# peripherals.net
KiCad netlist of a schematic drawn in Altium Designer
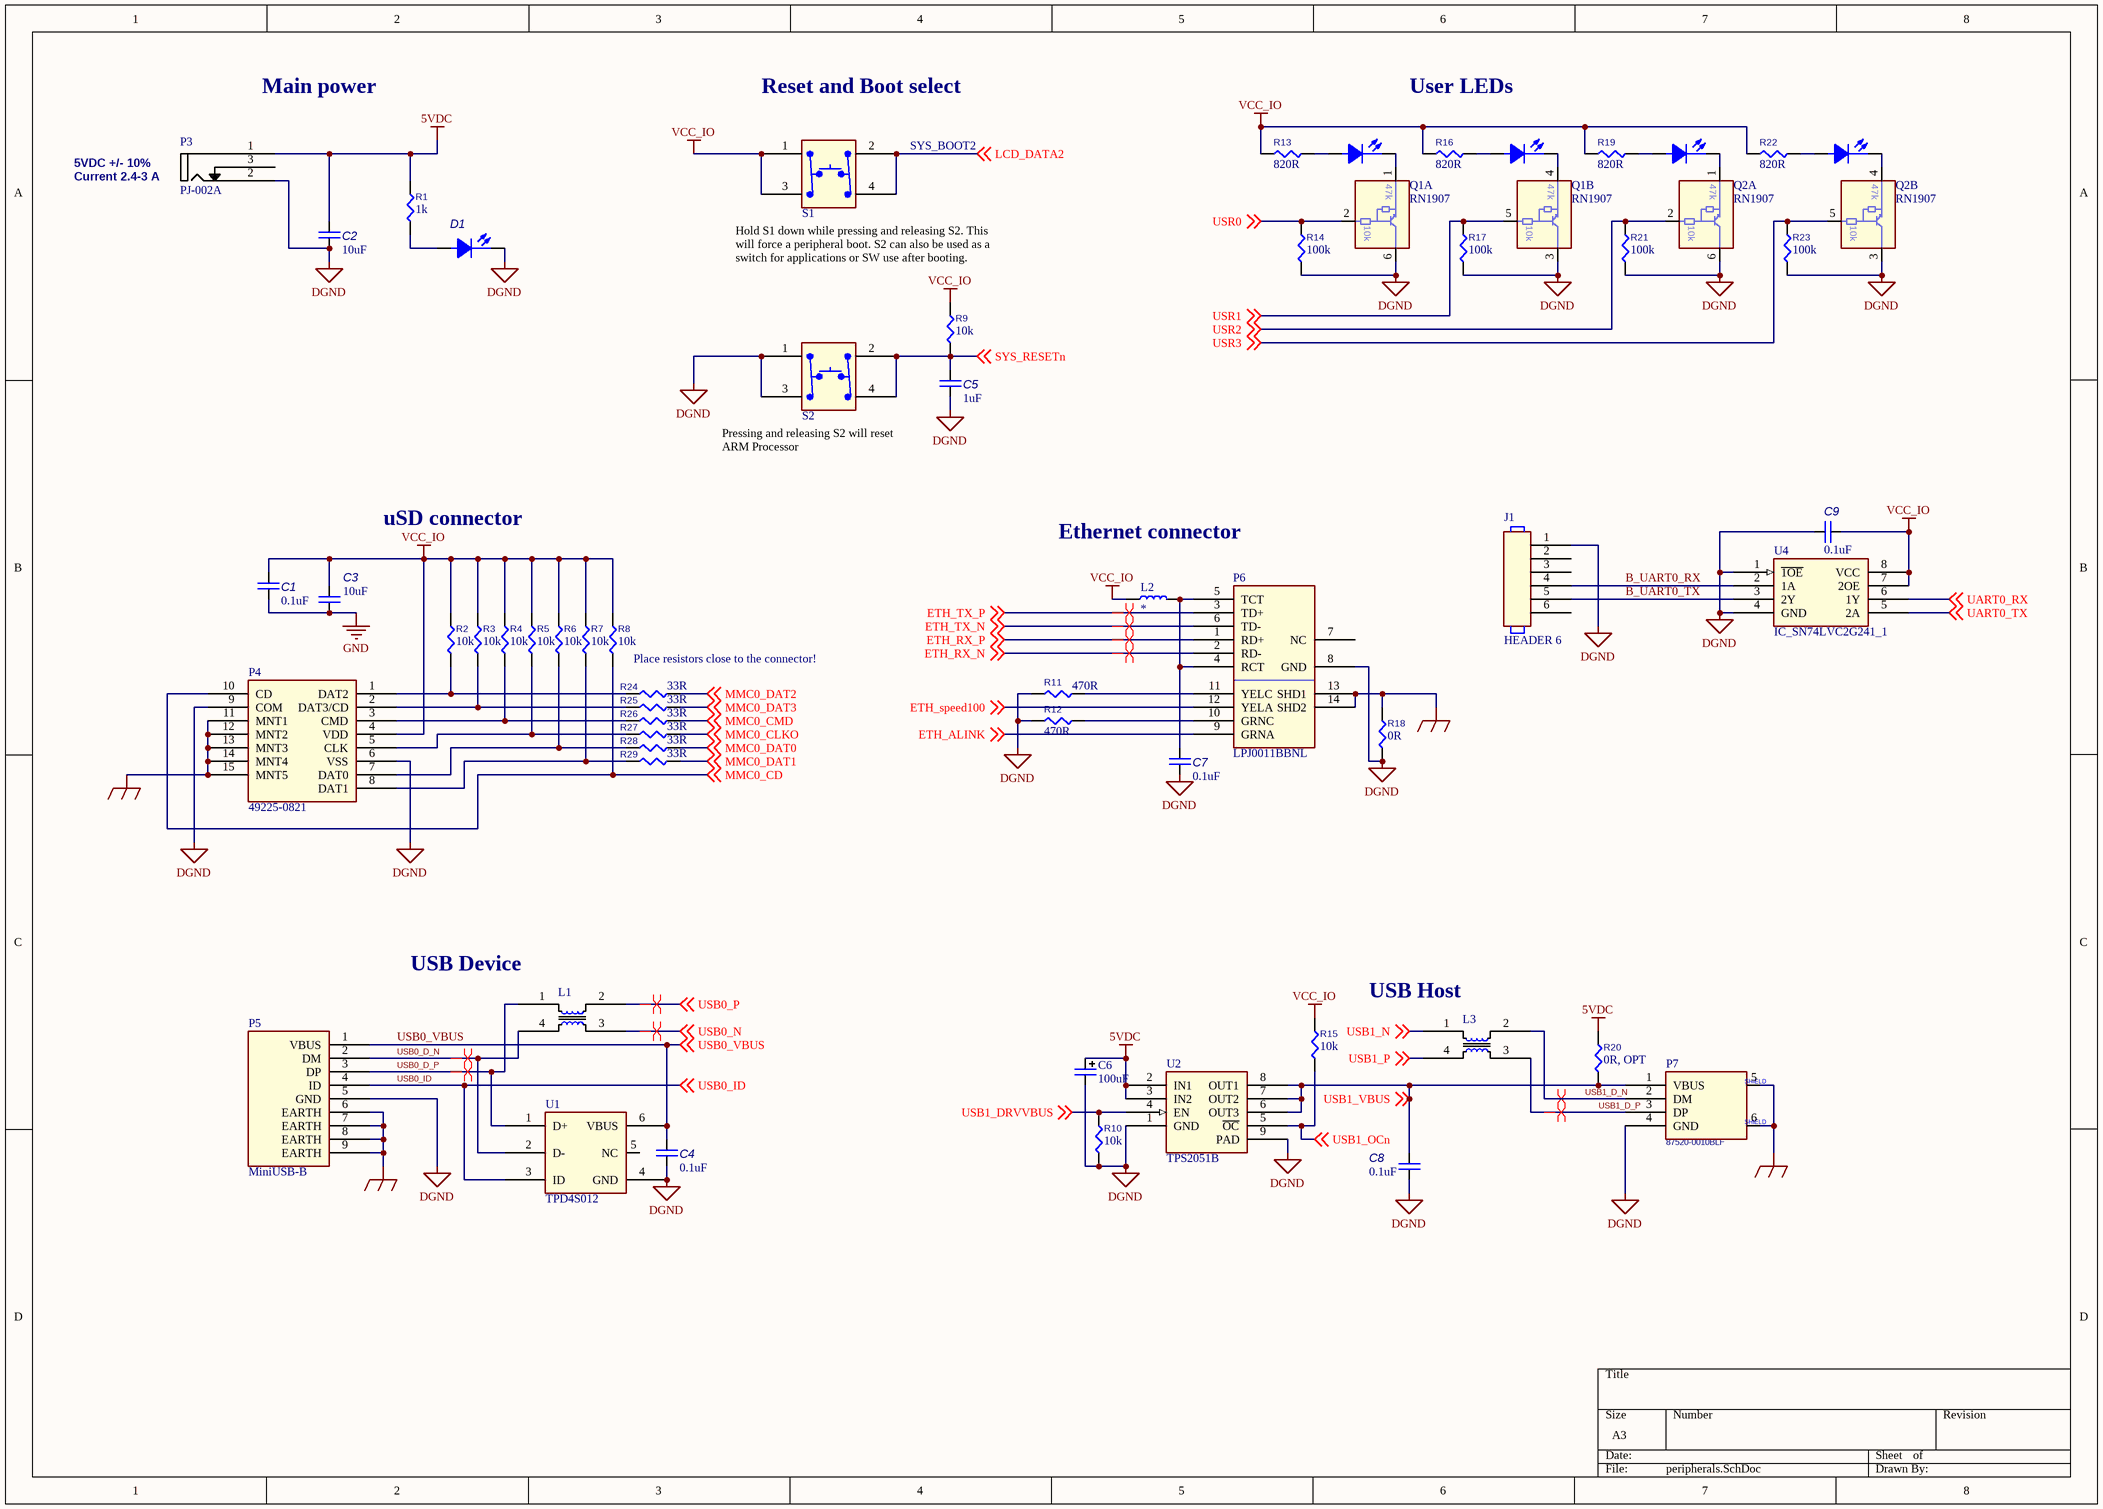
[diagram p0: peripherals.SchDoc]

(export (version "E")
  (design (tool "Eeschema 10.0.6"))
  (components
    (comp (ref "C1")
      (value "0.1uF")
      (footprint "CC1608-0603")
      (description "C0603")
      (libsource (lib "am335x-base") (part "C0603"))
    )
    (comp (ref "C2")
      (value "10uF")
      (footprint "CC2012-0805")
      (description "C0805")
      (libsource (lib "am335x-base") (part "C0805"))
    )
    (comp (ref "C3")
      (value "10uF")
      (footprint "CC2012-0805")
      (description "C0805")
      (libsource (lib "am335x-base") (part "C0805"))
    )
    (comp (ref "C4")
      (value "0.1uF")
      (footprint "CC1608-0603")
      (description "C0603")
      (libsource (lib "am335x-base") (part "C0603"))
    )
    (comp (ref "C5")
      (value "1uF")
      (footprint "CC1608-0603")
      (description "C0603")
      (libsource (lib "am335x-base") (part "C0603"))
    )
    (comp (ref "C6")
      (value "100uF")
      (footprint "Cap_C")
      (description "Tantalum Capacitor Case C")
      (fields (field (name "Comment") "Cap_C"))
      (libsource (lib "am335x-base") (part "Cap_C"))
    )
    (comp (ref "C7")
      (value "0.1uF")
      (footprint "CC1608-0603")
      (description "C0603")
      (libsource (lib "am335x-base") (part "C0603"))
    )
    (comp (ref "C8")
      (value "0.1uF")
      (footprint "CC1608-0603")
      (description "C0603")
      (libsource (lib "am335x-base") (part "C0603"))
    )
    (comp (ref "C9")
      (value "0.1uF")
      (footprint "CC1608-0603")
      (description "C0603")
      (libsource (lib "usomiq-base") (part "C0603"))
    )
    (comp (ref "D1")
      (value "LED0805")
      (footprint "LED0805")
      (description "LED 0805")
      (libsource (lib "am335x-base") (part "LED0805"))
    )
    (comp (ref "D2")
      (value "LED0805")
      (footprint "LED0805")
      (description "LED 0805")
      (libsource (lib "am335x-base") (part "LED0805"))
    )
    (comp (ref "D3")
      (value "LED0805")
      (footprint "LED0805")
      (description "LED 0805")
      (libsource (lib "am335x-base") (part "LED0805"))
    )
    (comp (ref "D4")
      (value "LED0805")
      (footprint "LED0805")
      (description "LED 0805")
      (libsource (lib "am335x-base") (part "LED0805"))
    )
    (comp (ref "D5")
      (value "LED0805")
      (footprint "LED0805")
      (description "LED 0805")
      (libsource (lib "am335x-base") (part "LED0805"))
    )
    (comp (ref "J1")
      (value "HEADER 6")
      (footprint "DIP6")
      (description "CONN HEADER 6POS, VERTICAL,  .100 STR TIN")
      (fields (field (name "MFR") "FCI"))
      (libsource (lib "usomiq-base") (part "HEADER 6"))
    )
    (comp (ref "L1")
      (value "DLW21H")
      (footprint "DLW21H")
      (description "Low profile wire-wound common choke coil")
      (fields (field (name "MANUFACTURER") "Murata"))
      (libsource (lib "am335x-base") (part "DLW21H"))
    )
    (comp (ref "L2")
      (value "BLM18A-FB")
      (footprint "CHIP0603")
      (description "Chip EMIFILr Inductor Type")
      (fields (field (name "MANUFACTURER") "Murata") (field (name "MAN P/N") "*"))
      (libsource (lib "am335x-base") (part "BLM18A-FB"))
    )
    (comp (ref "L3")
      (value "DLW21H")
      (footprint "DLW21H")
      (description "Low profile wire-wound common choke coil")
      (fields (field (name "MANUFACTURER") "Murata"))
      (libsource (lib "am335x-base") (part "DLW21H"))
    )
    (comp (ref "P3")
      (value "PJ-002A")
      (footprint "PJ-002A")
      (description "DC POWER JACK")
      (fields (field (name "MANUFACTURER") "CIU Inc"))
      (libsource (lib "omap") (part "PJ-002A"))
    )
    (comp (ref "P4")
      (value "49225-0821")
      (footprint "SDCard")
      (description "Connector for microSD™ Card (Push-push Type)")
      (fields (field (name "MANUFACTURER") "Molex"))
      (libsource (lib "am335x-base") (part "Mol_49225-0821"))
    )
    (comp (ref "P5")
      (value "MiniUSB-B")
      (footprint "MINI-USB-B5 SMT")
      (description "Mini USB Type B CONNECTOR")
      (fields (field (name "MFR") "Hirose"))
      (libsource (lib "usomiq-base") (part "MiniUSB-B"))
    )
    (comp (ref "P6")
      (value "CONN_RJ45_MAG_WE_0")
      (footprint "TRJ0011ABNL")
      (description "RJ-45 10/100 W/Magnetics")
      (fields (field (name "MFR") "Link PP") (field (name "P/N") "LPJ0011BBNL"))
      (libsource (lib "am335x-base") (part "CONN_RJ45_MAG_WE_0"))
    )
    (comp (ref "P7")
      (value "CONN_54819-0578_2")
      (footprint "USB2.5-2H4C")
      (description "USB Type A Connectors")
      (fields (field (name "P/N") "87520-0010BLF") (field (name "MFR") "FCI"))
      (libsource (lib "am335x-base") (part "CONN_54819-0578_2"))
    )
    (comp (ref "Q1")
      (value "RN1907")
      (footprint "SOT363-6L")
      (description "Transistor Silicon NPN")
      (fields (field (name "MFR") "Panasonic"))
      (libsource (lib "am335x-base") (part "RN1907"))
    )
    (comp (ref "Q2")
      (value "RN1907")
      (footprint "SOT363-6L")
      (description "Transistor Silicon NPN")
      (fields (field (name "MFR") "Panasonic"))
      (libsource (lib "am335x-base") (part "RN1907"))
    )
    (comp (ref "R1")
      (value "1k")
      (footprint "RESC1608X55N")
      (description "R0603")
      (libsource (lib "am335x-base") (part "R0603"))
    )
    (comp (ref "R2")
      (value "10k")
      (footprint "RESC1608X55N")
      (description "R0603")
      (libsource (lib "am335x-base") (part "R0603"))
    )
    (comp (ref "R3")
      (value "10k")
      (footprint "RESC1608X55N")
      (description "R0603")
      (libsource (lib "am335x-base") (part "R0603"))
    )
    (comp (ref "R4")
      (value "10k")
      (footprint "RESC1608X55N")
      (description "R0603")
      (libsource (lib "am335x-base") (part "R0603"))
    )
    (comp (ref "R5")
      (value "10k")
      (footprint "RESC1608X55N")
      (description "R0603")
      (libsource (lib "am335x-base") (part "R0603"))
    )
    (comp (ref "R6")
      (value "10k")
      (footprint "RESC1608X55N")
      (description "R0603")
      (libsource (lib "am335x-base") (part "R0603"))
    )
    (comp (ref "R7")
      (value "10k")
      (footprint "RESC1608X55N")
      (description "R0603")
      (libsource (lib "am335x-base") (part "R0603"))
    )
    (comp (ref "R8")
      (value "10k")
      (footprint "RESC1608X55N")
      (description "R0603")
      (libsource (lib "am335x-base") (part "R0603"))
    )
    (comp (ref "R9")
      (value "10k")
      (footprint "RESC1608X55N")
      (description "R0603")
      (libsource (lib "am335x-base") (part "R0603"))
    )
    (comp (ref "R10")
      (value "10k")
      (footprint "RESC1608X55N")
      (description "R0603")
      (libsource (lib "am335x-base") (part "R0603"))
    )
    (comp (ref "R11")
      (value "470R")
      (footprint "RESC1608X55N")
      (description "R0603")
      (libsource (lib "am335x-base") (part "R0603"))
    )
    (comp (ref "R12")
      (value "470R")
      (footprint "RESC1608X55N")
      (description "R0603")
      (libsource (lib "am335x-base") (part "R0603"))
    )
    (comp (ref "R13")
      (value "820R")
      (footprint "RESC1608X55N")
      (description "R0603")
      (libsource (lib "am335x-base") (part "R0603"))
    )
    (comp (ref "R14")
      (value "100k")
      (footprint "RESC1608X55N")
      (description "R0603")
      (libsource (lib "am335x-base") (part "R0603"))
    )
    (comp (ref "R15")
      (value "10k")
      (footprint "RESC1608X55N")
      (description "R0603")
      (libsource (lib "am335x-base") (part "R0603"))
    )
    (comp (ref "R16")
      (value "820R")
      (footprint "RESC1608X55N")
      (description "R0603")
      (libsource (lib "am335x-base") (part "R0603"))
    )
    (comp (ref "R17")
      (value "100k")
      (footprint "RESC1608X55N")
      (description "R0603")
      (libsource (lib "am335x-base") (part "R0603"))
    )
    (comp (ref "R18")
      (value "0R")
      (footprint "RESC1608X55N")
      (description "R0603")
      (libsource (lib "am335x-base") (part "R0603"))
    )
    (comp (ref "R19")
      (value "820R")
      (footprint "RESC1608X55N")
      (description "R0603")
      (libsource (lib "am335x-base") (part "R0603"))
    )
    (comp (ref "R20")
      (value "0R, OPT")
      (footprint "RESC1608X55N")
      (description "R0603")
      (libsource (lib "am335x-base") (part "R0603"))
    )
    (comp (ref "R21")
      (value "100k")
      (footprint "RESC1608X55N")
      (description "R0603")
      (libsource (lib "am335x-base") (part "R0603"))
    )
    (comp (ref "R22")
      (value "820R")
      (footprint "RESC1608X55N")
      (description "R0603")
      (libsource (lib "am335x-base") (part "R0603"))
    )
    (comp (ref "R23")
      (value "100k")
      (footprint "RESC1608X55N")
      (description "R0603")
      (libsource (lib "am335x-base") (part "R0603"))
    )
    (comp (ref "R24")
      (value "33R")
      (footprint "RESC1608X55N")
      (description "R0603")
      (libsource (lib "usomiq-base") (part "R0603"))
    )
    (comp (ref "R25")
      (value "33R")
      (footprint "RESC1608X55N")
      (description "R0603")
      (libsource (lib "usomiq-base") (part "R0603"))
    )
    (comp (ref "R26")
      (value "33R")
      (footprint "RESC1608X55N")
      (description "R0603")
      (libsource (lib "usomiq-base") (part "R0603"))
    )
    (comp (ref "R27")
      (value "33R")
      (footprint "RESC1608X55N")
      (description "R0603")
      (libsource (lib "usomiq-base") (part "R0603"))
    )
    (comp (ref "R28")
      (value "33R")
      (footprint "RESC1608X55N")
      (description "R0603")
      (libsource (lib "usomiq-base") (part "R0603"))
    )
    (comp (ref "R29")
      (value "33R")
      (footprint "RESC1608X55N")
      (description "R0603")
      (libsource (lib "usomiq-base") (part "R0603"))
    )
    (comp (ref "S1")
      (value "SW_KT11P2JM_2")
      (footprint "KMR231GLFS")
      (description "SMD button")
      (fields (field (name "MFR") "C&K Components"))
      (libsource (lib "usomiq-base") (part "SW_KT11P2JM_2"))
    )
    (comp (ref "S2")
      (value "SW_KT11P2JM_2")
      (footprint "KMR231GLFS")
      (description "SMD button")
      (fields (field (name "MFR") "C&K Components"))
      (libsource (lib "usomiq-base") (part "SW_KT11P2JM_2"))
    )
    (comp (ref "U1")
      (value "TPD4S012")
      (footprint "s-puson-n6")
      (description "4-Channel USB ESD Solution with Power Clamp")
      (fields (field (name "MFR") "TI"))
      (libsource (lib "usomiq-base") (part "TPD4S012"))
    )
    (comp (ref "U2")
      (value "TPS2051B")
      (footprint "R-PDSO-G8")
      (description "CURRENT-LIMITED, POWER-DISTRIBUTION SWITCHES")
      (fields (field (name "MFR") "TI"))
      (libsource (lib "usomiq-base") (part "TPS2051B"))
    )
    (comp (ref "U4")
      (value "IC_SN74LVC2G241_1")
      (footprint "SOP127P600-8N")
      (description "Dual Buffer/Driver With 3-State Outputs")
      (fields (field (name "MFR") "TI"))
      (libsource (lib "usomiq-base") (part "IC_SN74LVC2G241_1"))
    )
  )
  (nets
    (net (code "1") (name "/B_UART0_RX") (class "Default")
      (node (ref "J1") (pin "4") (pinfunction "4_4") (pintype "passive"))
      (node (ref "U4") (pin "2") (pinfunction "1A_2") (pintype "passive"))
    )
    (net (code "2") (name "/B_UART0_TX") (class "Default")
      (node (ref "J1") (pin "5") (pinfunction "5_5") (pintype "passive"))
      (node (ref "U4") (pin "3") (pinfunction "2Y_3") (pintype "passive"))
    )
    (net (code "3") (name "/USB0_D_N") (class "Default")
      (node (ref "L1") (pin "4") (pinfunction "4_4") (pintype "passive"))
      (node (ref "P5") (pin "2") (pinfunction "DM_2") (pintype "passive"))
      (node (ref "U1") (pin "2") (pinfunction "D-_2") (pintype "passive"))
    )
    (net (code "4") (name "/USB0_D_P") (class "Default")
      (node (ref "L1") (pin "1") (pinfunction "1_1") (pintype "passive"))
      (node (ref "P5") (pin "3") (pinfunction "DP_3") (pintype "passive"))
      (node (ref "U1") (pin "1") (pinfunction "D+_1") (pintype "passive"))
    )
    (net (code "5") (name "/USB1_D_N") (class "Default")
      (node (ref "L3") (pin "2") (pinfunction "2_2") (pintype "passive"))
      (node (ref "P7") (pin "2") (pinfunction "DM_2") (pintype "passive"))
    )
    (net (code "6") (name "/USB1_D_P") (class "Default")
      (node (ref "L3") (pin "3") (pinfunction "3_3") (pintype "passive"))
      (node (ref "P7") (pin "3") (pinfunction "DP_3") (pintype "passive"))
    )
    (net (code "7") (name "5VDC") (class "Default")
      (node (ref "C2") (pin "2") (pinfunction "2_2") (pintype "passive"))
      (node (ref "C6") (pin "1") (pinfunction "1_1") (pintype "passive"))
      (node (ref "P3") (pin "1") (pinfunction "GND_1") (pintype "passive"))
      (node (ref "R1") (pin "2") (pinfunction "2_2") (pintype "passive"))
      (node (ref "R20") (pin "2") (pinfunction "2_2") (pintype "passive"))
      (node (ref "U2") (pin "2") (pinfunction "IN1_2") (pintype "power_in"))
      (node (ref "U2") (pin "3") (pinfunction "IN2_3") (pintype "power_in"))
    )
    (net (code "8") (name "DGND") (class "Default")
      (node (ref "C2") (pin "1") (pinfunction "1_1") (pintype "passive"))
      (node (ref "C4") (pin "2") (pinfunction "2_2") (pintype "passive"))
      (node (ref "C5") (pin "2") (pinfunction "2_2") (pintype "passive"))
      (node (ref "C6") (pin "2") (pinfunction "2_2") (pintype "passive"))
      (node (ref "C7") (pin "2") (pinfunction "2_2") (pintype "passive"))
      (node (ref "C8") (pin "1") (pinfunction "1_1") (pintype "passive"))
      (node (ref "C9") (pin "1") (pinfunction "1_1") (pintype "passive"))
      (node (ref "D1") (pin "2") (pinfunction "C_2") (pintype "passive"))
      (node (ref "J1") (pin "1") (pinfunction "1_1") (pintype "passive"))
      (node (ref "P3") (pin "2") (pinfunction "RIGHT_2") (pintype "passive"))
      (node (ref "P4") (pin "6") (pinfunction "VSS_6") (pintype "power_in"))
      (node (ref "P4") (pin "9") (pinfunction "COM_9") (pintype "passive"))
      (node (ref "P5") (pin "5") (pinfunction "GND_5") (pintype "power_in"))
      (node (ref "P6") (pin "8") (pinfunction "GND_8") (pintype "passive"))
      (node (ref "P7") (pin "4") (pinfunction "GND_4") (pintype "passive"))
      (node (ref "Q1") (pin "3") (pinfunction "3_3") (pintype "passive"))
      (node (ref "Q1") (pin "6") (pinfunction "3_6") (pintype "passive"))
      (node (ref "Q2") (pin "3") (pinfunction "3_3") (pintype "passive"))
      (node (ref "Q2") (pin "6") (pinfunction "3_6") (pintype "passive"))
      (node (ref "R10") (pin "1") (pinfunction "1_1") (pintype "passive"))
      (node (ref "R11") (pin "1") (pinfunction "1_1") (pintype "passive"))
      (node (ref "R12") (pin "1") (pinfunction "1_1") (pintype "passive"))
      (node (ref "R14") (pin "1") (pinfunction "1_1") (pintype "passive"))
      (node (ref "R17") (pin "1") (pinfunction "1_1") (pintype "passive"))
      (node (ref "R18") (pin "1") (pinfunction "1_1") (pintype "passive"))
      (node (ref "R21") (pin "1") (pinfunction "1_1") (pintype "passive"))
      (node (ref "R23") (pin "1") (pinfunction "1_1") (pintype "passive"))
      (node (ref "S2") (pin "1") (pinfunction "A1_1") (pintype "passive"))
      (node (ref "S2") (pin "3") (pinfunction "A2_3") (pintype "passive"))
      (node (ref "U1") (pin "4") (pinfunction "GND_4") (pintype "power_in"))
      (node (ref "U2") (pin "1") (pinfunction "GND_1") (pintype "power_in"))
      (node (ref "U2") (pin "9") (pinfunction "PAD_9") (pintype "passive"))
      (node (ref "U4") (pin "1") (pinfunction "~{1OE}_1") (pintype "input"))
      (node (ref "U4") (pin "4") (pinfunction "GND_4") (pintype "power_in"))
    )
    (net (code "9") (name "EARTH") (class "Default")
      (node (ref "P4") (pin "11") (pinfunction "MNT1_11") (pintype "passive"))
      (node (ref "P4") (pin "12") (pinfunction "MNT2_12") (pintype "passive"))
      (node (ref "P4") (pin "13") (pinfunction "MNT3_13") (pintype "passive"))
      (node (ref "P4") (pin "14") (pinfunction "MNT4_14") (pintype "passive"))
      (node (ref "P4") (pin "15") (pinfunction "MNT5_15") (pintype "passive"))
      (node (ref "P5") (pin "6") (pinfunction "EARTH_6") (pintype "passive"))
      (node (ref "P5") (pin "7") (pinfunction "EARTH_7") (pintype "passive"))
      (node (ref "P5") (pin "8") (pinfunction "EARTH_8") (pintype "passive"))
      (node (ref "P5") (pin "9") (pinfunction "EARTH_9") (pintype "passive"))
      (node (ref "P6") (pin "13") (pinfunction "SHD1_13") (pintype "passive"))
      (node (ref "P6") (pin "14") (pinfunction "SHD2_14") (pintype "passive"))
      (node (ref "P7") (pin "5") (pinfunction "SHELD1_5") (pintype "passive"))
      (node (ref "P7") (pin "6") (pinfunction "PAD4_6") (pintype "passive"))
      (node (ref "R18") (pin "2") (pinfunction "2_2") (pintype "passive"))
    )
    (net (code "10") (name "ETH_ALINK") (class "Default")
      (node (ref "P6") (pin "9") (pinfunction "GRNA_9") (pintype "passive"))
    )
    (net (code "11") (name "ETH_RX_N") (class "Default")
      (node (ref "P6") (pin "2") (pinfunction "RD-_2") (pintype "passive"))
    )
    (net (code "12") (name "ETH_RX_P") (class "Default")
      (node (ref "P6") (pin "1") (pinfunction "RD+_1") (pintype "passive"))
    )
    (net (code "13") (name "ETH_TX_N") (class "Default")
      (node (ref "P6") (pin "6") (pinfunction "TD-_6") (pintype "passive"))
    )
    (net (code "14") (name "ETH_TX_P") (class "Default")
      (node (ref "P6") (pin "3") (pinfunction "TD+_3") (pintype "passive"))
    )
    (net (code "15") (name "ETH_speed100") (class "Default")
      (node (ref "P6") (pin "12") (pinfunction "YELA_12") (pintype "passive"))
    )
    (net (code "16") (name "GND") (class "Default")
      (node (ref "C1") (pin "2") (pinfunction "2_2") (pintype "passive"))
      (node (ref "C3") (pin "1") (pinfunction "1_1") (pintype "passive"))
    )
    (net (code "17") (name "LCD_DATA2") (class "Default")
      (node (ref "S1") (pin "2") (pinfunction "B1_2") (pintype "passive"))
      (node (ref "S1") (pin "4") (pinfunction "B2_4") (pintype "passive"))
    )
    (net (code "18") (name "MMC0_CD") (class "Default")
      (node (ref "P4") (pin "10") (pinfunction "CD_10") (pintype "passive"))
      (node (ref "R8") (pin "1") (pinfunction "1_1") (pintype "passive"))
    )
    (net (code "19") (name "MMC0_CLKO") (class "Default")
      (node (ref "R27") (pin "2") (pinfunction "2_2") (pintype "passive"))
    )
    (net (code "20") (name "MMC0_CMD") (class "Default")
      (node (ref "R26") (pin "2") (pinfunction "2_2") (pintype "passive"))
    )
    (net (code "21") (name "MMC0_DAT0") (class "Default")
      (node (ref "R28") (pin "2") (pinfunction "2_2") (pintype "passive"))
    )
    (net (code "22") (name "MMC0_DAT1") (class "Default")
      (node (ref "R29") (pin "2") (pinfunction "2_2") (pintype "passive"))
    )
    (net (code "23") (name "MMC0_DAT2") (class "Default")
      (node (ref "R24") (pin "2") (pinfunction "2_2") (pintype "passive"))
    )
    (net (code "24") (name "MMC0_DAT3") (class "Default")
      (node (ref "R25") (pin "2") (pinfunction "2_2") (pintype "passive"))
    )
    (net (code "25") (name "Net-(D1-A)") (class "Default")
      (node (ref "D1") (pin "1") (pinfunction "A_1") (pintype "passive"))
      (node (ref "R1") (pin "1") (pinfunction "1_1") (pintype "passive"))
    )
    (net (code "26") (name "Net-(D2-A)") (class "Default")
      (node (ref "D2") (pin "1") (pinfunction "A_1") (pintype "passive"))
      (node (ref "R13") (pin "1") (pinfunction "1_1") (pintype "passive"))
    )
    (net (code "27") (name "Net-(D2-C)") (class "Default")
      (node (ref "D2") (pin "2") (pinfunction "C_2") (pintype "passive"))
      (node (ref "Q1") (pin "1") (pinfunction "4_1") (pintype "passive"))
    )
    (net (code "28") (name "Net-(D3-A)") (class "Default")
      (node (ref "D3") (pin "1") (pinfunction "A_1") (pintype "passive"))
      (node (ref "R16") (pin "1") (pinfunction "1_1") (pintype "passive"))
    )
    (net (code "29") (name "Net-(D3-C)") (class "Default")
      (node (ref "D3") (pin "2") (pinfunction "C_2") (pintype "passive"))
      (node (ref "Q1") (pin "4") (pinfunction "4_4") (pintype "passive"))
    )
    (net (code "30") (name "Net-(D4-A)") (class "Default")
      (node (ref "D4") (pin "1") (pinfunction "A_1") (pintype "passive"))
      (node (ref "R19") (pin "1") (pinfunction "1_1") (pintype "passive"))
    )
    (net (code "31") (name "Net-(D4-C)") (class "Default")
      (node (ref "D4") (pin "2") (pinfunction "C_2") (pintype "passive"))
      (node (ref "Q2") (pin "1") (pinfunction "4_1") (pintype "passive"))
    )
    (net (code "32") (name "Net-(D5-A)") (class "Default")
      (node (ref "D5") (pin "1") (pinfunction "A_1") (pintype "passive"))
      (node (ref "R22") (pin "1") (pinfunction "1_1") (pintype "passive"))
    )
    (net (code "33") (name "Net-(D5-C)") (class "Default")
      (node (ref "D5") (pin "2") (pinfunction "C_2") (pintype "passive"))
      (node (ref "Q2") (pin "4") (pinfunction "4_4") (pintype "passive"))
    )
    (net (code "34") (name "Net-(P4-CLK)") (class "Default")
      (node (ref "P4") (pin "5") (pinfunction "CLK_5") (pintype "passive"))
      (node (ref "R27") (pin "1") (pinfunction "1_1") (pintype "passive"))
      (node (ref "R5") (pin "1") (pinfunction "1_1") (pintype "passive"))
    )
    (net (code "35") (name "Net-(P4-CMD)") (class "Default")
      (node (ref "P4") (pin "3") (pinfunction "CMD_3") (pintype "passive"))
      (node (ref "R26") (pin "1") (pinfunction "1_1") (pintype "passive"))
      (node (ref "R4") (pin "1") (pinfunction "1_1") (pintype "passive"))
    )
    (net (code "36") (name "Net-(P4-DAT0)") (class "Default")
      (node (ref "P4") (pin "7") (pinfunction "DAT0_7") (pintype "passive"))
      (node (ref "R28") (pin "1") (pinfunction "1_1") (pintype "passive"))
      (node (ref "R6") (pin "1") (pinfunction "1_1") (pintype "passive"))
    )
    (net (code "37") (name "Net-(P4-DAT1)") (class "Default")
      (node (ref "P4") (pin "8") (pinfunction "DAT1_8") (pintype "passive"))
      (node (ref "R29") (pin "1") (pinfunction "1_1") (pintype "passive"))
      (node (ref "R7") (pin "1") (pinfunction "1_1") (pintype "passive"))
    )
    (net (code "38") (name "Net-(P4-DAT2)") (class "Default")
      (node (ref "P4") (pin "1") (pinfunction "DAT2_1") (pintype "passive"))
      (node (ref "R2") (pin "1") (pinfunction "1_1") (pintype "passive"))
      (node (ref "R24") (pin "1") (pinfunction "1_1") (pintype "passive"))
    )
    (net (code "39") (name "Net-(P4-DAT3{slash}CD)") (class "Default")
      (node (ref "P4") (pin "2") (pinfunction "DAT3/CD_2") (pintype "passive"))
      (node (ref "R25") (pin "1") (pinfunction "1_1") (pintype "passive"))
      (node (ref "R3") (pin "1") (pinfunction "1_1") (pintype "passive"))
    )
    (net (code "40") (name "Net-(P6-GRNC)") (class "Default")
      (node (ref "P6") (pin "10") (pinfunction "GRNC_10") (pintype "passive"))
      (node (ref "R12") (pin "2") (pinfunction "2_2") (pintype "passive"))
    )
    (net (code "41") (name "Net-(P6-RCT)") (class "Default")
      (node (ref "C7") (pin "1") (pinfunction "1_1") (pintype "passive"))
      (node (ref "L2") (pin "2") (pinfunction "2_2") (pintype "passive"))
      (node (ref "P6") (pin "4") (pinfunction "RCT_4") (pintype "passive"))
      (node (ref "P6") (pin "5") (pinfunction "TCT_5") (pintype "passive"))
    )
    (net (code "42") (name "Net-(P6-YELC)") (class "Default")
      (node (ref "P6") (pin "11") (pinfunction "YELC_11") (pintype "passive"))
      (node (ref "R11") (pin "2") (pinfunction "2_2") (pintype "passive"))
    )
    (net (code "43") (name "SYS_RESETn") (class "Default")
      (node (ref "C5") (pin "1") (pinfunction "1_1") (pintype "passive"))
      (node (ref "R9") (pin "1") (pinfunction "1_1") (pintype "passive"))
      (node (ref "S2") (pin "2") (pinfunction "B1_2") (pintype "passive"))
      (node (ref "S2") (pin "4") (pinfunction "B2_4") (pintype "passive"))
    )
    (net (code "44") (name "UART0_RX") (class "Default")
      (node (ref "U4") (pin "6") (pinfunction "1Y_6") (pintype "passive"))
    )
    (net (code "45") (name "UART0_TX") (class "Default")
      (node (ref "U4") (pin "5") (pinfunction "2A_5") (pintype "passive"))
    )
    (net (code "46") (name "USB0_ID") (class "Default")
      (node (ref "P5") (pin "4") (pinfunction "ID_4") (pintype "passive"))
      (node (ref "U1") (pin "3") (pinfunction "ID_3") (pintype "passive"))
    )
    (net (code "47") (name "USB0_N") (class "Default")
      (node (ref "L1") (pin "3") (pinfunction "3_3") (pintype "passive"))
    )
    (net (code "48") (name "USB0_P") (class "Default")
      (node (ref "L1") (pin "2") (pinfunction "2_2") (pintype "passive"))
    )
    (net (code "49") (name "USB0_VBUS") (class "Default")
      (node (ref "C4") (pin "1") (pinfunction "1_1") (pintype "passive"))
      (node (ref "P5") (pin "1") (pinfunction "VBUS_1") (pintype "power_in"))
      (node (ref "U1") (pin "6") (pinfunction "VBUS_6") (pintype "power_in"))
    )
    (net (code "50") (name "USB1_DRVVBUS") (class "Default")
      (node (ref "R10") (pin "2") (pinfunction "2_2") (pintype "passive"))
      (node (ref "U2") (pin "4") (pinfunction "EN_4") (pintype "input"))
    )
    (net (code "51") (name "USB1_N") (class "Default")
      (node (ref "L3") (pin "1") (pinfunction "1_1") (pintype "passive"))
    )
    (net (code "52") (name "USB1_OCn") (class "Default")
      (node (ref "R15") (pin "1") (pinfunction "1_1") (pintype "passive"))
      (node (ref "U2") (pin "5") (pinfunction "~{OC}_5") (pintype "passive"))
    )
    (net (code "53") (name "USB1_P") (class "Default")
      (node (ref "L3") (pin "4") (pinfunction "4_4") (pintype "passive"))
    )
    (net (code "54") (name "USB1_VBUS") (class "Default")
      (node (ref "C8") (pin "2") (pinfunction "2_2") (pintype "passive"))
      (node (ref "P7") (pin "1") (pinfunction "VBUS_1") (pintype "passive"))
      (node (ref "R20") (pin "1") (pinfunction "1_1") (pintype "passive"))
      (node (ref "U2") (pin "6") (pinfunction "OUT3_6") (pintype "power_in"))
      (node (ref "U2") (pin "7") (pinfunction "OUT2_7") (pintype "power_in"))
      (node (ref "U2") (pin "8") (pinfunction "OUT1_8") (pintype "power_in"))
    )
    (net (code "55") (name "USR0") (class "Default")
      (node (ref "Q1") (pin "2") (pinfunction "5_2") (pintype "passive"))
      (node (ref "R14") (pin "2") (pinfunction "2_2") (pintype "passive"))
    )
    (net (code "56") (name "USR1") (class "Default")
      (node (ref "Q1") (pin "5") (pinfunction "5_5") (pintype "passive"))
      (node (ref "R17") (pin "2") (pinfunction "2_2") (pintype "passive"))
    )
    (net (code "57") (name "USR2") (class "Default")
      (node (ref "Q2") (pin "2") (pinfunction "5_2") (pintype "passive"))
      (node (ref "R21") (pin "2") (pinfunction "2_2") (pintype "passive"))
    )
    (net (code "58") (name "USR3") (class "Default")
      (node (ref "Q2") (pin "5") (pinfunction "5_5") (pintype "passive"))
      (node (ref "R23") (pin "2") (pinfunction "2_2") (pintype "passive"))
    )
    (net (code "59") (name "VCC_IO") (class "Default")
      (node (ref "C1") (pin "1") (pinfunction "1_1") (pintype "passive"))
      (node (ref "C3") (pin "2") (pinfunction "2_2") (pintype "passive"))
      (node (ref "C9") (pin "2") (pinfunction "2_2") (pintype "passive"))
      (node (ref "L2") (pin "1") (pinfunction "1_1") (pintype "passive"))
      (node (ref "P4") (pin "4") (pinfunction "VDD_4") (pintype "power_in"))
      (node (ref "R13") (pin "2") (pinfunction "2_2") (pintype "passive"))
      (node (ref "R15") (pin "2") (pinfunction "2_2") (pintype "passive"))
      (node (ref "R16") (pin "2") (pinfunction "2_2") (pintype "passive"))
      (node (ref "R19") (pin "2") (pinfunction "2_2") (pintype "passive"))
      (node (ref "R2") (pin "2") (pinfunction "2_2") (pintype "passive"))
      (node (ref "R22") (pin "2") (pinfunction "2_2") (pintype "passive"))
      (node (ref "R3") (pin "2") (pinfunction "2_2") (pintype "passive"))
      (node (ref "R4") (pin "2") (pinfunction "2_2") (pintype "passive"))
      (node (ref "R5") (pin "2") (pinfunction "2_2") (pintype "passive"))
      (node (ref "R6") (pin "2") (pinfunction "2_2") (pintype "passive"))
      (node (ref "R7") (pin "2") (pinfunction "2_2") (pintype "passive"))
      (node (ref "R8") (pin "2") (pinfunction "2_2") (pintype "passive"))
      (node (ref "R9") (pin "2") (pinfunction "2_2") (pintype "passive"))
      (node (ref "S1") (pin "1") (pinfunction "A1_1") (pintype "passive"))
      (node (ref "S1") (pin "3") (pinfunction "A2_3") (pintype "passive"))
      (node (ref "U4") (pin "7") (pinfunction "2OE_7") (pintype "passive"))
      (node (ref "U4") (pin "8") (pinfunction "VCC_8") (pintype "power_in"))
    )
    (net (code "60") (name "unconnected-(J1-Pad2)") (class "Default")
      (node (ref "J1") (pin "2") (pinfunction "2_2") (pintype "passive"))
    )
    (net (code "61") (name "unconnected-(J1-Pad3)") (class "Default")
      (node (ref "J1") (pin "3") (pinfunction "3_3") (pintype "passive"))
    )
    (net (code "62") (name "unconnected-(J1-Pad6)") (class "Default")
      (node (ref "J1") (pin "6") (pinfunction "6_6") (pintype "passive"))
    )
    (net (code "63") (name "unconnected-(P3-LEFT-Pad3)") (class "Default")
      (node (ref "P3") (pin "3") (pinfunction "LEFT_3") (pintype "passive"))
    )
    (net (code "64") (name "unconnected-(P6-NC-Pad7)") (class "Default")
      (node (ref "P6") (pin "7") (pinfunction "NC_7") (pintype "passive"))
    )
    (net (code "65") (name "unconnected-(U1-NC-Pad5)") (class "Default")
      (node (ref "U1") (pin "5") (pinfunction "NC_5") (pintype "passive"))
    )
  )
)
